# RP_Sapling.net
KiCad netlist of a schematic drawn in EAGLE
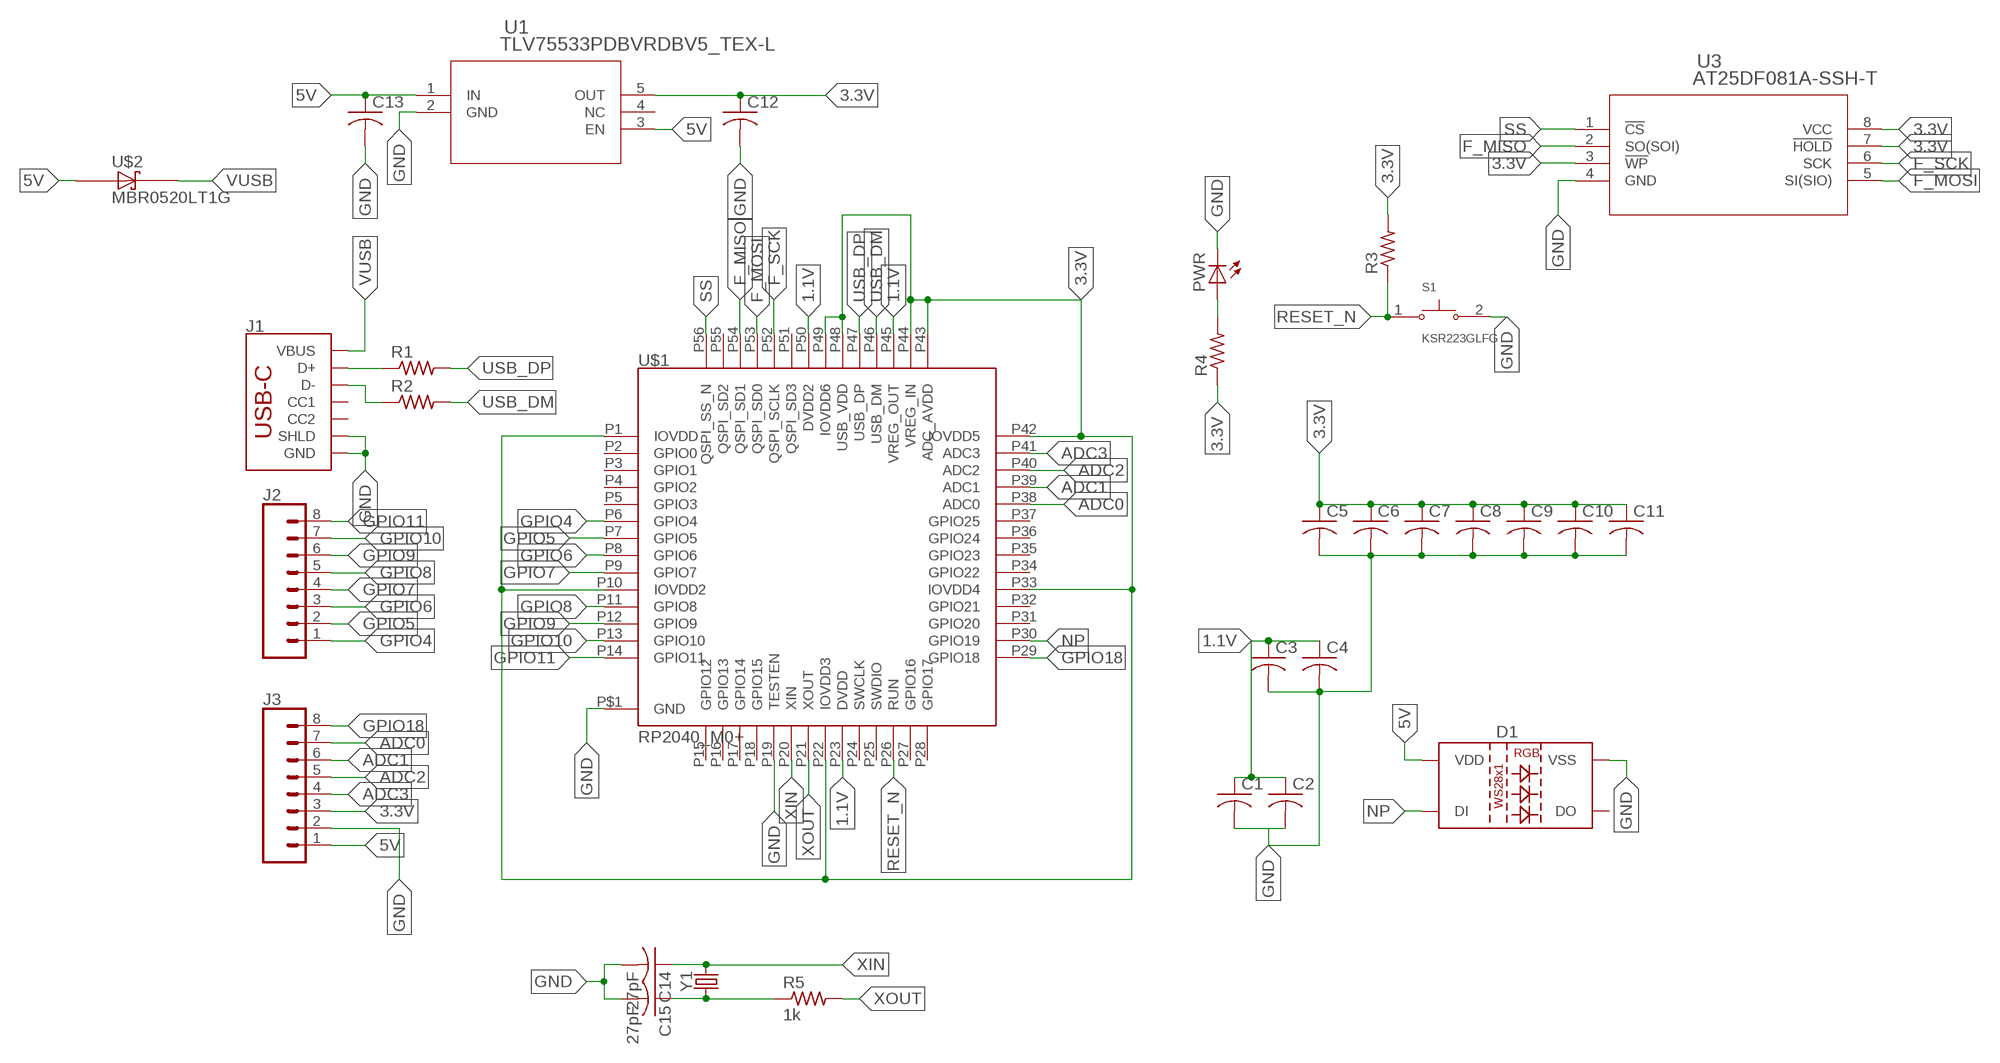
[diagram p0: schematic, sheet 1]

(export (version "E")
  (design (tool "Eeschema 10.0.6"))
  (components
    (comp (ref "C1")
      (value "C-USC0402")
      (footprint "eagle-import:C0402")
      (libsource (lib "eagle-import") (part "C-USC0402"))
    )
    (comp (ref "C2")
      (value "C-USC0402")
      (footprint "eagle-import:C0402")
      (libsource (lib "eagle-import") (part "C-USC0402"))
    )
    (comp (ref "C3")
      (value "C-USC0402")
      (footprint "eagle-import:C0402")
      (libsource (lib "eagle-import") (part "C-USC0402"))
    )
    (comp (ref "C4")
      (value "C-USC0402")
      (footprint "eagle-import:C0402")
      (libsource (lib "eagle-import") (part "C-USC0402"))
    )
    (comp (ref "C5")
      (value "C-USC0402")
      (footprint "eagle-import:C0402")
      (libsource (lib "eagle-import") (part "C-USC0402"))
    )
    (comp (ref "C6")
      (value "C-USC0402")
      (footprint "eagle-import:C0402")
      (libsource (lib "eagle-import") (part "C-USC0402"))
    )
    (comp (ref "C7")
      (value "C-USC0402")
      (footprint "eagle-import:C0402")
      (libsource (lib "eagle-import") (part "C-USC0402"))
    )
    (comp (ref "C8")
      (value "C-USC0402")
      (footprint "eagle-import:C0402")
      (libsource (lib "eagle-import") (part "C-USC0402"))
    )
    (comp (ref "C9")
      (value "C-USC0402")
      (footprint "eagle-import:C0402")
      (libsource (lib "eagle-import") (part "C-USC0402"))
    )
    (comp (ref "C10")
      (value "C-USC0402")
      (footprint "eagle-import:C0402")
      (libsource (lib "eagle-import") (part "C-USC0402"))
    )
    (comp (ref "C11")
      (value "C-USC0402")
      (footprint "eagle-import:C0402")
      (libsource (lib "eagle-import") (part "C-USC0402"))
    )
    (comp (ref "C12")
      (value "C-USC0402")
      (footprint "eagle-import:C0402")
      (libsource (lib "eagle-import") (part "C-USC0402"))
    )
    (comp (ref "C13")
      (value "C-USC0402")
      (footprint "eagle-import:C0402")
      (libsource (lib "eagle-import") (part "C-USC0402"))
    )
    (comp (ref "C14")
      (value "27pF")
      (footprint "eagle-import:C0402")
      (libsource (lib "eagle-import") (part "C-USC0402"))
    )
    (comp (ref "C15")
      (value "27pF")
      (footprint "eagle-import:C0402")
      (libsource (lib "eagle-import") (part "C-USC0402"))
    )
    (comp (ref "D1")
      (value "WS2812BWS2812B-1515")
      (footprint "eagle-import:WS2812B-1515")
      (libsource (lib "eagle-import") (part "WS2812BWS2812B-1515"))
    )
    (comp (ref "J1")
      (value "USB_C_2-LAYER")
      (footprint "eagle-import:USB-C-16P")
      (libsource (lib "eagle-import") (part "USB_C_2-LAYER"))
    )
    (comp (ref "J2")
      (value "CONN_08NO_SILK_DNP")
      (footprint "eagle-import:1X08_NO_SILK")
      (libsource (lib "eagle-import") (part "CONN_08NO_SILK_DNP"))
    )
    (comp (ref "J3")
      (value "CONN_08NO_SILK_DNP")
      (footprint "eagle-import:1X08_NO_SILK")
      (libsource (lib "eagle-import") (part "CONN_08NO_SILK_DNP"))
    )
    (comp (ref "PWR")
      (value "LEDCHIPLED_0805")
      (footprint "eagle-import:CHIPLED_0805")
      (libsource (lib "eagle-import") (part "LEDCHIPLED_0805"))
    )
    (comp (ref "R1")
      (value "R-US_R0603")
      (footprint "eagle-import:R0603")
      (libsource (lib "eagle-import") (part "R-US_R0603"))
    )
    (comp (ref "R2")
      (value "R-US_R0603")
      (footprint "eagle-import:R0603")
      (libsource (lib "eagle-import") (part "R-US_R0603"))
    )
    (comp (ref "R3")
      (value "R-US_R0402")
      (footprint "eagle-import:R0402")
      (libsource (lib "eagle-import") (part "R-US_R0402"))
    )
    (comp (ref "R4")
      (value "R-US_R0603")
      (footprint "eagle-import:R0603")
      (libsource (lib "eagle-import") (part "R-US_R0603"))
    )
    (comp (ref "R5")
      (value "1k")
      (footprint "eagle-import:R0402")
      (libsource (lib "eagle-import") (part "R-US_R0402"))
    )
    (comp (ref "S1")
      (value "KSR223GLFG")
      (footprint "eagle-import:SW_KSR223GLFG")
      (fields (field (name "MF") "C&K"))
      (libsource (lib "eagle-import") (part "KSR223GLFG"))
    )
    (comp (ref "U$1")
      (value "RP2040_M0+")
      (footprint "eagle-import:QFN-56")
      (libsource (lib "eagle-import") (part "RP2040_M0+"))
    )
    (comp (ref "U$2")
      (value "MBR0520LT1G")
      (footprint "eagle-import:SOD3716X117(SOD-123)")
      (fields (field (name "MF") "ON Semiconductor"))
      (libsource (lib "eagle-import") (part "MBR0520LT1G"))
    )
    (comp (ref "U1")
      (value "TLV75533PDBVRDBV5_TEX-L")
      (footprint "eagle-import:DBV5_TEX-L")
      (fields
        (field (name "MANUFACTURER_PART_NUMBER") "TLV75533PDBVR")
        (field (name "COPYRIGHT") "Copyright (C) 2018 Accelerated Designs. All rights reserved")
      )
      (libsource (lib "eagle-import") (part "TLV75533PDBVRDBV5_TEX-L"))
    )
    (comp (ref "U3")
      (value "AT25DF081A-SSH-T")
      (footprint "eagle-import:SOIC_AT25DF081_ADO")
      (fields (field (name "COPYRIGHT") "Copyright (C) 2018 Accelerated Designs. All rights reserved"))
      (libsource (lib "eagle-import") (part "AT25DF081A-SSH-T"))
    )
    (comp (ref "Y1")
      (value "CRYSTALSMD-5X3.2-2PAD")
      (footprint "eagle-import:CRYSTAL-SMD-5X3.2-2PAD")
      (libsource (lib "eagle-import") (part "CRYSTALSMD-5X3.2-2PAD"))
    )
  )
  (nets
    (net (code "1") (name "1.1V") (class "Default")
      (node (ref "C1") (pin "1") (pinfunction "1_1") (pintype "passive"))
      (node (ref "C2") (pin "1") (pinfunction "1_1") (pintype "passive"))
      (node (ref "C3") (pin "1") (pinfunction "1_1") (pintype "passive"))
      (node (ref "C4") (pin "1") (pinfunction "1_1") (pintype "passive"))
      (node (ref "U$1") (pin "P23") (pinfunction "DVDD_P23") (pintype "bidirectional"))
      (node (ref "U$1") (pin "P45") (pinfunction "VREG_OUT_P45") (pintype "bidirectional"))
      (node (ref "U$1") (pin "P50") (pinfunction "DVDD2_P50") (pintype "bidirectional"))
    )
    (net (code "2") (name "3.3V") (class "Default")
      (node (ref "C10") (pin "1") (pinfunction "1_1") (pintype "passive"))
      (node (ref "C11") (pin "1") (pinfunction "1_1") (pintype "passive"))
      (node (ref "C12") (pin "1") (pinfunction "1_1") (pintype "passive"))
      (node (ref "C5") (pin "1") (pinfunction "1_1") (pintype "passive"))
      (node (ref "C6") (pin "1") (pinfunction "1_1") (pintype "passive"))
      (node (ref "C7") (pin "1") (pinfunction "1_1") (pintype "passive"))
      (node (ref "C8") (pin "1") (pinfunction "1_1") (pintype "passive"))
      (node (ref "C9") (pin "1") (pinfunction "1_1") (pintype "passive"))
      (node (ref "J3") (pin "3") (pinfunction "3_3") (pintype "passive"))
      (node (ref "R3") (pin "2") (pinfunction "2_2") (pintype "passive"))
      (node (ref "R4") (pin "1") (pinfunction "1_1") (pintype "passive"))
      (node (ref "U$1") (pin "P1") (pinfunction "IOVDD_P1") (pintype "bidirectional"))
      (node (ref "U$1") (pin "P10") (pinfunction "IOVDD2_P10") (pintype "bidirectional"))
      (node (ref "U$1") (pin "P22") (pinfunction "IOVDD3_P22") (pintype "bidirectional"))
      (node (ref "U$1") (pin "P33") (pinfunction "IOVDD4_P33") (pintype "bidirectional"))
      (node (ref "U$1") (pin "P42") (pinfunction "IOVDD5_P42") (pintype "bidirectional"))
      (node (ref "U$1") (pin "P43") (pinfunction "ADC_AVDD_P43") (pintype "bidirectional"))
      (node (ref "U$1") (pin "P44") (pinfunction "VREG_IN_P44") (pintype "bidirectional"))
      (node (ref "U$1") (pin "P48") (pinfunction "USB_VDD_P48") (pintype "bidirectional"))
      (node (ref "U$1") (pin "P49") (pinfunction "IOVDD6_P49") (pintype "bidirectional"))
      (node (ref "U1") (pin "5") (pinfunction "OUT_5") (pintype "output"))
      (node (ref "U3") (pin "3") (pinfunction "~{WP}_3") (pintype "input"))
      (node (ref "U3") (pin "7") (pinfunction "~{HOLD}_7") (pintype "input"))
      (node (ref "U3") (pin "8") (pinfunction "VCC_8") (pintype "power_in"))
    )
    (net (code "3") (name "5V") (class "Default")
      (node (ref "C13") (pin "1") (pinfunction "1_1") (pintype "passive"))
      (node (ref "D1") (pin "VDD") (pinfunction "VDD_VDD") (pintype "bidirectional"))
      (node (ref "J3") (pin "1") (pinfunction "1_1") (pintype "passive"))
      (node (ref "U$2") (pin "2") (pinfunction "A_2") (pintype "passive"))
      (node (ref "U1") (pin "1") (pinfunction "IN_1") (pintype "input"))
      (node (ref "U1") (pin "3") (pinfunction "EN_3") (pintype "input"))
    )
    (net (code "4") (name "ADC0") (class "Default")
      (node (ref "J3") (pin "7") (pinfunction "7_7") (pintype "passive"))
      (node (ref "U$1") (pin "P38") (pinfunction "ADC0_P38") (pintype "bidirectional"))
    )
    (net (code "5") (name "ADC1") (class "Default")
      (node (ref "J3") (pin "6") (pinfunction "6_6") (pintype "passive"))
      (node (ref "U$1") (pin "P39") (pinfunction "ADC1_P39") (pintype "bidirectional"))
    )
    (net (code "6") (name "ADC2") (class "Default")
      (node (ref "J3") (pin "5") (pinfunction "5_5") (pintype "passive"))
      (node (ref "U$1") (pin "P40") (pinfunction "ADC2_P40") (pintype "bidirectional"))
    )
    (net (code "7") (name "ADC3") (class "Default")
      (node (ref "J3") (pin "4") (pinfunction "4_4") (pintype "passive"))
      (node (ref "U$1") (pin "P41") (pinfunction "ADC3_P41") (pintype "bidirectional"))
    )
    (net (code "8") (name "F_MISO") (class "Default")
      (node (ref "U$1") (pin "P54") (pinfunction "QSPI_SD1_P54") (pintype "bidirectional"))
      (node (ref "U3") (pin "2") (pinfunction "SO(SOI)_2") (pintype "bidirectional"))
    )
    (net (code "9") (name "F_MOSI") (class "Default")
      (node (ref "U$1") (pin "P53") (pinfunction "QSPI_SD0_P53") (pintype "bidirectional"))
      (node (ref "U3") (pin "5") (pinfunction "SI(SIO)_5") (pintype "bidirectional"))
    )
    (net (code "10") (name "F_SCK") (class "Default")
      (node (ref "U$1") (pin "P52") (pinfunction "QSPI_SCLK_P52") (pintype "bidirectional"))
      (node (ref "U3") (pin "6") (pinfunction "SCK_6") (pintype "input"))
    )
    (net (code "11") (name "GND") (class "Default")
      (node (ref "C1") (pin "2") (pinfunction "2_2") (pintype "passive"))
      (node (ref "C10") (pin "2") (pinfunction "2_2") (pintype "passive"))
      (node (ref "C11") (pin "2") (pinfunction "2_2") (pintype "passive"))
      (node (ref "C12") (pin "2") (pinfunction "2_2") (pintype "passive"))
      (node (ref "C13") (pin "2") (pinfunction "2_2") (pintype "passive"))
      (node (ref "C14") (pin "2") (pinfunction "2_2") (pintype "passive"))
      (node (ref "C15") (pin "2") (pinfunction "2_2") (pintype "passive"))
      (node (ref "C2") (pin "2") (pinfunction "2_2") (pintype "passive"))
      (node (ref "C3") (pin "2") (pinfunction "2_2") (pintype "passive"))
      (node (ref "C4") (pin "2") (pinfunction "2_2") (pintype "passive"))
      (node (ref "C5") (pin "2") (pinfunction "2_2") (pintype "passive"))
      (node (ref "C6") (pin "2") (pinfunction "2_2") (pintype "passive"))
      (node (ref "C7") (pin "2") (pinfunction "2_2") (pintype "passive"))
      (node (ref "C8") (pin "2") (pinfunction "2_2") (pintype "passive"))
      (node (ref "C9") (pin "2") (pinfunction "2_2") (pintype "passive"))
      (node (ref "D1") (pin "GND") (pinfunction "VSS_GND") (pintype "bidirectional"))
      (node (ref "J1") (pin "GND") (pinfunction "GND_GND") (pintype "bidirectional"))
      (node (ref "J1") (pin "GND2") (pinfunction "GND_GND2") (pintype "bidirectional"))
      (node (ref "J1") (pin "SHLD1") (pinfunction "SHLD_SHLD1") (pintype "bidirectional"))
      (node (ref "J1") (pin "SHLD2") (pinfunction "SHLD_SHLD2") (pintype "bidirectional"))
      (node (ref "J1") (pin "SHLD3") (pinfunction "SHLD_SHLD3") (pintype "bidirectional"))
      (node (ref "J1") (pin "SHLD4") (pinfunction "SHLD_SHLD4") (pintype "bidirectional"))
      (node (ref "J1") (pin "SHLD5") (pinfunction "SHLD_SHLD5") (pintype "bidirectional"))
      (node (ref "J1") (pin "SHLD6") (pinfunction "SHLD_SHLD6") (pintype "bidirectional"))
      (node (ref "J1") (pin "SHLD7") (pinfunction "SHLD_SHLD7") (pintype "bidirectional"))
      (node (ref "J1") (pin "SHLD8") (pinfunction "SHLD_SHLD8") (pintype "bidirectional"))
      (node (ref "J3") (pin "2") (pinfunction "2_2") (pintype "passive"))
      (node (ref "PWR") (pin "C") (pinfunction "C_C") (pintype "passive"))
      (node (ref "S1") (pin "2") (pinfunction "2_2") (pintype "passive"))
      (node (ref "U$1") (pin "P$1") (pinfunction "GND_P$1") (pintype "bidirectional"))
      (node (ref "U$1") (pin "P19") (pinfunction "TESTEN_P19") (pintype "bidirectional"))
      (node (ref "U1") (pin "2") (pinfunction "GND_2") (pintype "power_in"))
      (node (ref "U3") (pin "4") (pinfunction "GND_4") (pintype "power_in"))
    )
    (net (code "12") (name "GPIO4") (class "Default")
      (node (ref "J2") (pin "1") (pinfunction "1_1") (pintype "passive"))
      (node (ref "U$1") (pin "P6") (pinfunction "GPIO4_P6") (pintype "bidirectional"))
    )
    (net (code "13") (name "GPIO5") (class "Default")
      (node (ref "J2") (pin "2") (pinfunction "2_2") (pintype "passive"))
      (node (ref "U$1") (pin "P7") (pinfunction "GPIO5_P7") (pintype "bidirectional"))
    )
    (net (code "14") (name "GPIO6") (class "Default")
      (node (ref "J2") (pin "3") (pinfunction "3_3") (pintype "passive"))
      (node (ref "U$1") (pin "P8") (pinfunction "GPIO6_P8") (pintype "bidirectional"))
    )
    (net (code "15") (name "GPIO7") (class "Default")
      (node (ref "J2") (pin "4") (pinfunction "4_4") (pintype "passive"))
      (node (ref "U$1") (pin "P9") (pinfunction "GPIO7_P9") (pintype "bidirectional"))
    )
    (net (code "16") (name "GPIO8") (class "Default")
      (node (ref "J2") (pin "5") (pinfunction "5_5") (pintype "passive"))
      (node (ref "U$1") (pin "P11") (pinfunction "GPIO8_P11") (pintype "bidirectional"))
    )
    (net (code "17") (name "GPIO9") (class "Default")
      (node (ref "J2") (pin "6") (pinfunction "6_6") (pintype "passive"))
      (node (ref "U$1") (pin "P12") (pinfunction "GPIO9_P12") (pintype "bidirectional"))
    )
    (net (code "18") (name "GPIO10") (class "Default")
      (node (ref "J2") (pin "7") (pinfunction "7_7") (pintype "passive"))
      (node (ref "U$1") (pin "P13") (pinfunction "GPIO10_P13") (pintype "bidirectional"))
    )
    (net (code "19") (name "GPIO11") (class "Default")
      (node (ref "J2") (pin "8") (pinfunction "8_8") (pintype "passive"))
      (node (ref "U$1") (pin "P14") (pinfunction "GPIO11_P14") (pintype "bidirectional"))
    )
    (net (code "20") (name "GPIO18") (class "Default")
      (node (ref "J3") (pin "8") (pinfunction "8_8") (pintype "passive"))
      (node (ref "U$1") (pin "P29") (pinfunction "GPIO18_P29") (pintype "bidirectional"))
    )
    (net (code "21") (name "NP") (class "Default")
      (node (ref "D1") (pin "DIN") (pinfunction "DI_DIN") (pintype "bidirectional"))
      (node (ref "U$1") (pin "P30") (pinfunction "GPIO19_P30") (pintype "bidirectional"))
    )
    (net (code "22") (name "Net-(J1-D+-PadA6)") (class "Default")
      (node (ref "J1") (pin "A6") (pinfunction "D+_A6") (pintype "bidirectional"))
      (node (ref "J1") (pin "B6") (pinfunction "D+_B6") (pintype "bidirectional"))
      (node (ref "R1") (pin "1") (pinfunction "1_1") (pintype "passive"))
    )
    (net (code "23") (name "Net-(J1-D--PadA7)") (class "Default")
      (node (ref "J1") (pin "A7") (pinfunction "D-_A7") (pintype "bidirectional"))
      (node (ref "J1") (pin "B7") (pinfunction "D-_B7") (pintype "bidirectional"))
      (node (ref "R2") (pin "1") (pinfunction "1_1") (pintype "passive"))
    )
    (net (code "24") (name "Net-(PWR-PadA)") (class "Default")
      (node (ref "PWR") (pin "A") (pinfunction "A_A") (pintype "passive"))
      (node (ref "R4") (pin "2") (pinfunction "2_2") (pintype "passive"))
    )
    (net (code "25") (name "Net-(Y1-1)") (class "Default")
      (node (ref "C15") (pin "1") (pinfunction "1_1") (pintype "passive"))
      (node (ref "R5") (pin "1") (pinfunction "1_1") (pintype "passive"))
      (node (ref "Y1") (pin "P$1") (pinfunction "1_P$1") (pintype "passive"))
    )
    (net (code "26") (name "RESET_N") (class "Default")
      (node (ref "R3") (pin "1") (pinfunction "1_1") (pintype "passive"))
      (node (ref "S1") (pin "1") (pinfunction "1_1") (pintype "passive"))
      (node (ref "U$1") (pin "P26") (pinfunction "RUN_P26") (pintype "bidirectional"))
    )
    (net (code "27") (name "SS") (class "Default")
      (node (ref "U$1") (pin "P56") (pinfunction "QSPI_SS_N_P56") (pintype "bidirectional"))
      (node (ref "U3") (pin "1") (pinfunction "~{CS}_1") (pintype "input"))
    )
    (net (code "28") (name "USB_DM") (class "Default")
      (node (ref "R2") (pin "2") (pinfunction "2_2") (pintype "passive"))
      (node (ref "U$1") (pin "P46") (pinfunction "USB_DM_P46") (pintype "bidirectional"))
    )
    (net (code "29") (name "USB_DP") (class "Default")
      (node (ref "R1") (pin "2") (pinfunction "2_2") (pintype "passive"))
      (node (ref "U$1") (pin "P47") (pinfunction "USB_DP_P47") (pintype "bidirectional"))
    )
    (net (code "30") (name "VUSB") (class "Default")
      (node (ref "J1") (pin "VBUS1") (pinfunction "VBUS_VBUS1") (pintype "bidirectional"))
      (node (ref "J1") (pin "VBUS2") (pinfunction "VBUS_VBUS2") (pintype "bidirectional"))
      (node (ref "U$2") (pin "1") (pinfunction "C_1") (pintype "passive"))
    )
    (net (code "31") (name "XIN") (class "Default")
      (node (ref "C14") (pin "1") (pinfunction "1_1") (pintype "passive"))
      (node (ref "U$1") (pin "P20") (pinfunction "XIN_P20") (pintype "bidirectional"))
      (node (ref "Y1") (pin "P$2") (pinfunction "2_P$2") (pintype "passive"))
    )
    (net (code "32") (name "XOUT") (class "Default")
      (node (ref "R5") (pin "2") (pinfunction "2_2") (pintype "passive"))
      (node (ref "U$1") (pin "P21") (pinfunction "XOUT_P21") (pintype "bidirectional"))
    )
    (net (code "33") (name "unconnected-(D1-DO-PadDOUT)") (class "Default")
      (node (ref "D1") (pin "DOUT") (pinfunction "DO_DOUT") (pintype "bidirectional"))
    )
    (net (code "34") (name "unconnected-(J1-CC1-PadA5)") (class "Default")
      (node (ref "J1") (pin "A5") (pinfunction "CC1_A5") (pintype "bidirectional"))
    )
    (net (code "35") (name "unconnected-(J1-CC2-PadB5)") (class "Default")
      (node (ref "J1") (pin "B5") (pinfunction "CC2_B5") (pintype "bidirectional"))
    )
    (net (code "36") (name "unconnected-(U$1-GPIO0-PadP2)") (class "Default")
      (node (ref "U$1") (pin "P2") (pinfunction "GPIO0_P2") (pintype "bidirectional"))
    )
    (net (code "37") (name "unconnected-(U$1-GPIO1-PadP3)") (class "Default")
      (node (ref "U$1") (pin "P3") (pinfunction "GPIO1_P3") (pintype "bidirectional"))
    )
    (net (code "38") (name "unconnected-(U$1-GPIO2-PadP4)") (class "Default")
      (node (ref "U$1") (pin "P4") (pinfunction "GPIO2_P4") (pintype "bidirectional"))
    )
    (net (code "39") (name "unconnected-(U$1-GPIO3-PadP5)") (class "Default")
      (node (ref "U$1") (pin "P5") (pinfunction "GPIO3_P5") (pintype "bidirectional"))
    )
    (net (code "40") (name "unconnected-(U$1-GPIO12-PadP15)") (class "Default")
      (node (ref "U$1") (pin "P15") (pinfunction "GPIO12_P15") (pintype "bidirectional"))
    )
    (net (code "41") (name "unconnected-(U$1-GPIO13-PadP16)") (class "Default")
      (node (ref "U$1") (pin "P16") (pinfunction "GPIO13_P16") (pintype "bidirectional"))
    )
    (net (code "42") (name "unconnected-(U$1-GPIO14-PadP17)") (class "Default")
      (node (ref "U$1") (pin "P17") (pinfunction "GPIO14_P17") (pintype "bidirectional"))
    )
    (net (code "43") (name "unconnected-(U$1-GPIO15-PadP18)") (class "Default")
      (node (ref "U$1") (pin "P18") (pinfunction "GPIO15_P18") (pintype "bidirectional"))
    )
    (net (code "44") (name "unconnected-(U$1-GPIO16-PadP27)") (class "Default")
      (node (ref "U$1") (pin "P27") (pinfunction "GPIO16_P27") (pintype "bidirectional"))
    )
    (net (code "45") (name "unconnected-(U$1-GPIO17-PadP28)") (class "Default")
      (node (ref "U$1") (pin "P28") (pinfunction "GPIO17_P28") (pintype "bidirectional"))
    )
    (net (code "46") (name "unconnected-(U$1-GPIO20-PadP31)") (class "Default")
      (node (ref "U$1") (pin "P31") (pinfunction "GPIO20_P31") (pintype "bidirectional"))
    )
    (net (code "47") (name "unconnected-(U$1-GPIO21-PadP32)") (class "Default")
      (node (ref "U$1") (pin "P32") (pinfunction "GPIO21_P32") (pintype "bidirectional"))
    )
    (net (code "48") (name "unconnected-(U$1-GPIO22-PadP34)") (class "Default")
      (node (ref "U$1") (pin "P34") (pinfunction "GPIO22_P34") (pintype "bidirectional"))
    )
    (net (code "49") (name "unconnected-(U$1-GPIO23-PadP35)") (class "Default")
      (node (ref "U$1") (pin "P35") (pinfunction "GPIO23_P35") (pintype "bidirectional"))
    )
    (net (code "50") (name "unconnected-(U$1-GPIO24-PadP36)") (class "Default")
      (node (ref "U$1") (pin "P36") (pinfunction "GPIO24_P36") (pintype "bidirectional"))
    )
    (net (code "51") (name "unconnected-(U$1-GPIO25-PadP37)") (class "Default")
      (node (ref "U$1") (pin "P37") (pinfunction "GPIO25_P37") (pintype "bidirectional"))
    )
    (net (code "52") (name "unconnected-(U$1-QSPI_SD2-PadP55)") (class "Default")
      (node (ref "U$1") (pin "P55") (pinfunction "QSPI_SD2_P55") (pintype "bidirectional"))
    )
    (net (code "53") (name "unconnected-(U$1-QSPI_SD3-PadP51)") (class "Default")
      (node (ref "U$1") (pin "P51") (pinfunction "QSPI_SD3_P51") (pintype "bidirectional"))
    )
    (net (code "54") (name "unconnected-(U$1-SWCLK-PadP24)") (class "Default")
      (node (ref "U$1") (pin "P24") (pinfunction "SWCLK_P24") (pintype "bidirectional"))
    )
    (net (code "55") (name "unconnected-(U$1-SWDIO-PadP25)") (class "Default")
      (node (ref "U$1") (pin "P25") (pinfunction "SWDIO_P25") (pintype "bidirectional"))
    )
    (net (code "56") (name "unconnected-(U1-NC-Pad4)") (class "Default")
      (node (ref "U1") (pin "4") (pinfunction "NC_4") (pintype "no_connect"))
    )
  )
)
